# openSX70-dongle_v2-9.net
KiCad netlist of a schematic drawn in EAGLE
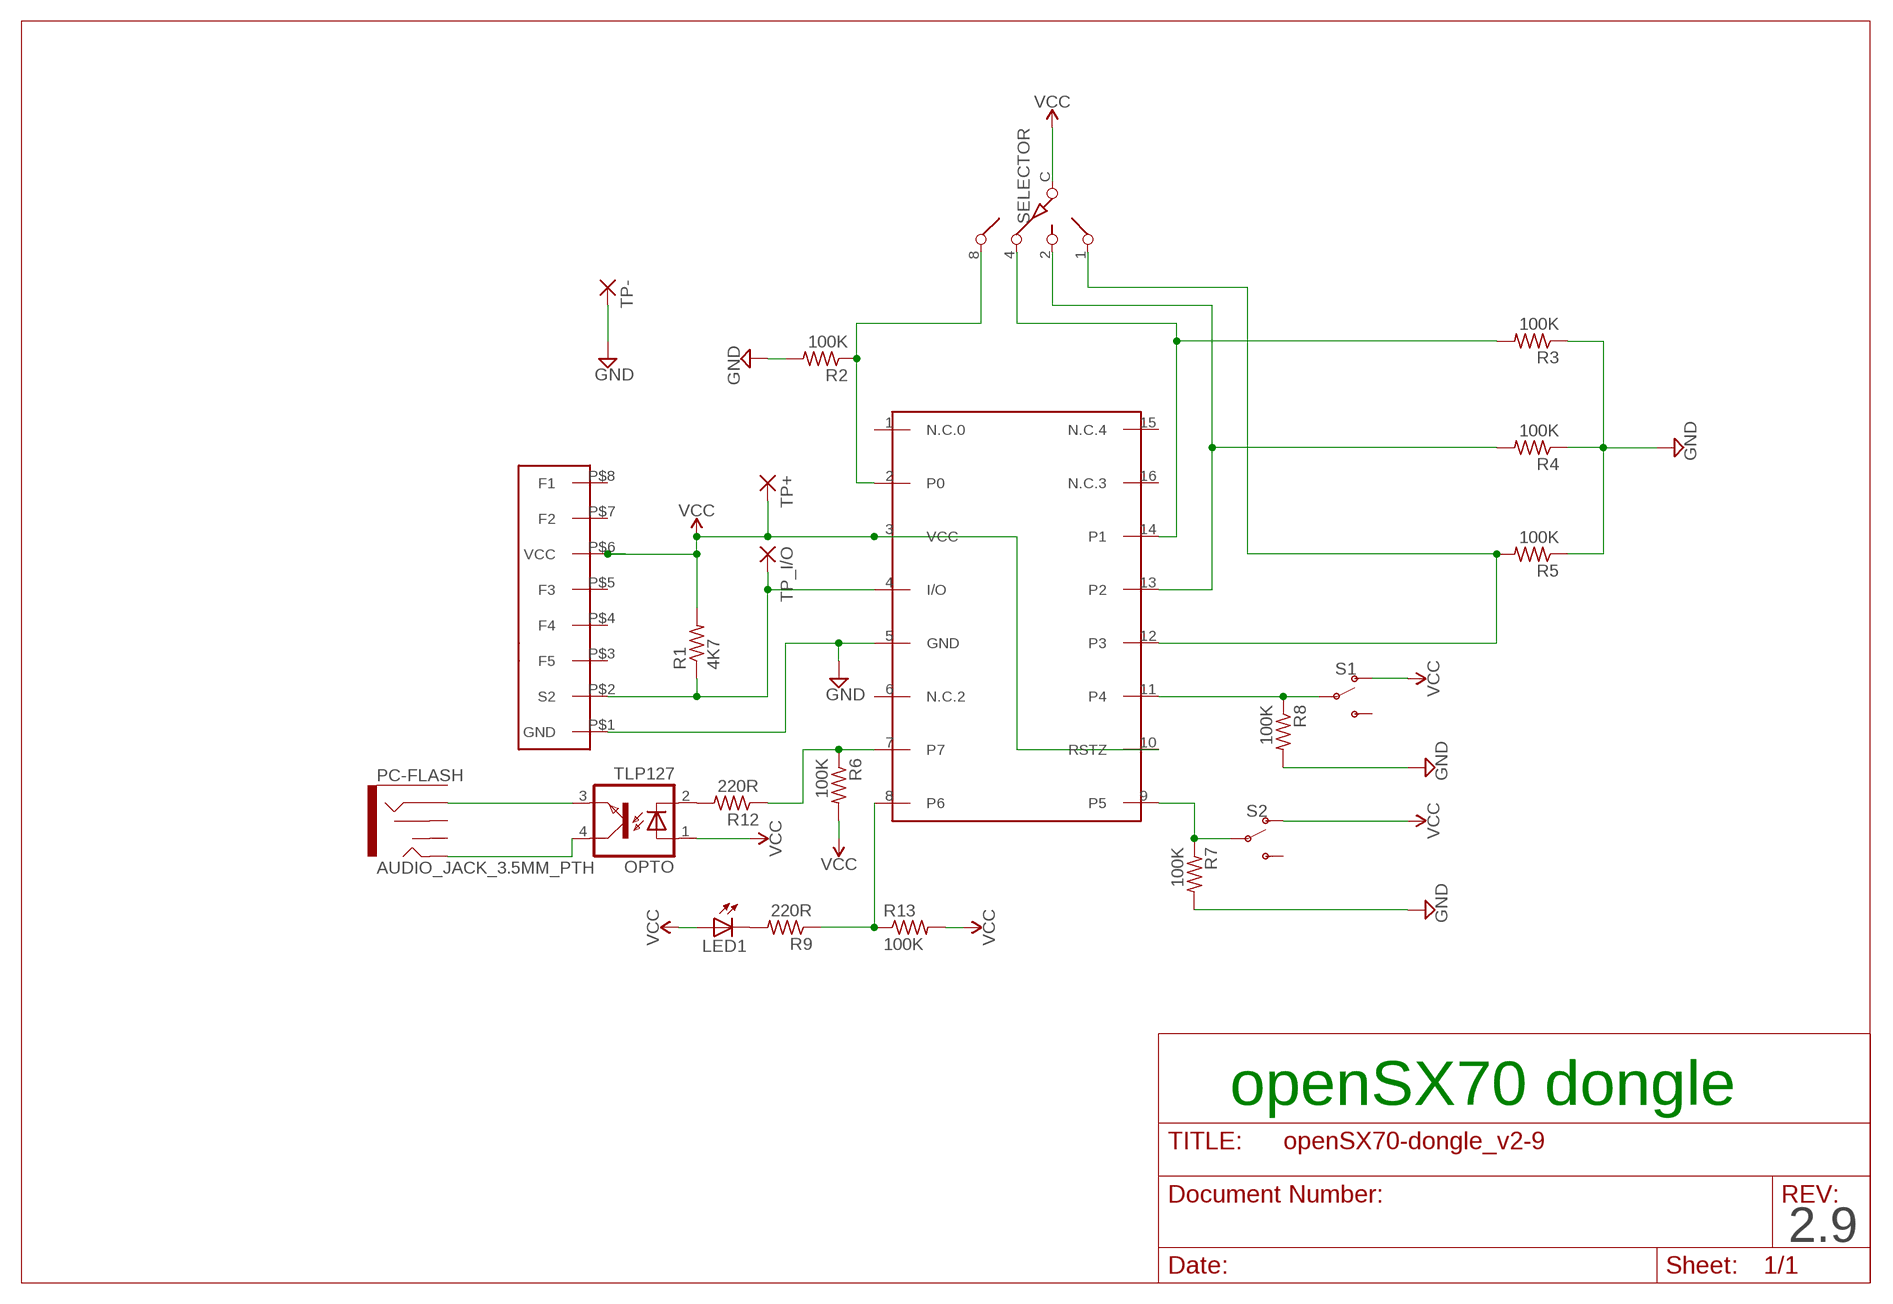
[diagram p0: schematic, sheet 1]

(export (version "E")
  (design (tool "Eeschema 10.0.6"))
  (components
    (comp (ref "DS2408")
      (value "DS2408")
      (footprint "eagle-import:SO16")
      (libsource (lib "eagle-import") (part "DS2408"))
    )
    (comp (ref "LED1")
      (value "LED3MM")
      (footprint "eagle-import:LED3MM")
      (libsource (lib "eagle-import") (part "LED3MM"))
    )
    (comp (ref "OPTO")
      (value "TLP127")
      (footprint "eagle-import:SO-4")
      (libsource (lib "eagle-import") (part "TLP127"))
    )
    (comp (ref "PC-FLASH")
      (value "AUDIO_JACK_3.5MM_PTH")
      (footprint "eagle-import:AUDIO-JACK")
      (libsource (lib "eagle-import") (part "AUDIO_JACK_3.5MM_PTH"))
    )
    (comp (ref "R1")
      (value "4K7")
      (footprint "eagle-import:M0805")
      (libsource (lib "eagle-import") (part "R-US_M0805"))
    )
    (comp (ref "R2")
      (value "100K")
      (footprint "eagle-import:M0805")
      (libsource (lib "eagle-import") (part "R-US_M0805"))
    )
    (comp (ref "R3")
      (value "100K")
      (footprint "eagle-import:M0805")
      (libsource (lib "eagle-import") (part "R-US_M0805"))
    )
    (comp (ref "R4")
      (value "100K")
      (footprint "eagle-import:M0805")
      (libsource (lib "eagle-import") (part "R-US_M0805"))
    )
    (comp (ref "R5")
      (value "100K")
      (footprint "eagle-import:M0805")
      (libsource (lib "eagle-import") (part "R-US_M0805"))
    )
    (comp (ref "R6")
      (value "100K")
      (footprint "eagle-import:M0805")
      (libsource (lib "eagle-import") (part "R-US_M0805"))
    )
    (comp (ref "R7")
      (value "100K")
      (footprint "eagle-import:M0805")
      (libsource (lib "eagle-import") (part "R-US_M0805"))
    )
    (comp (ref "R8")
      (value "100K")
      (footprint "eagle-import:M0805")
      (libsource (lib "eagle-import") (part "R-US_M0805"))
    )
    (comp (ref "R9")
      (value "220R")
      (footprint "eagle-import:M0805")
      (libsource (lib "eagle-import") (part "R-US_M0805"))
    )
    (comp (ref "R12")
      (value "220R")
      (footprint "eagle-import:M0805")
      (libsource (lib "eagle-import") (part "R-US_M0805"))
    )
    (comp (ref "R13")
      (value "100K")
      (footprint "eagle-import:M0805")
      (libsource (lib "eagle-import") (part "R-US_M0805"))
    )
    (comp (ref "S1")
      (value "SWITCH-SPDT-SMD-RIGHT-ANGLE")
      (footprint "eagle-import:SWITCH_SPST_SMD_A")
      (libsource (lib "eagle-import") (part "SWITCH-SPDT-SMD-RIGHT-ANGLE"))
    )
    (comp (ref "S2")
      (value "SWITCH-SPDT-SMD-RIGHT-ANGLE")
      (footprint "eagle-import:SWITCH_SPST_SMD_A")
      (libsource (lib "eagle-import") (part "SWITCH-SPDT-SMD-RIGHT-ANGLE"))
    )
    (comp (ref "SELECTOR")
      (value "SW-C16")
      (footprint "eagle-import:SW-C16")
      (libsource (lib "eagle-import") (part "SW-C16"))
    )
    (comp (ref "TP+")
      (value "SMD2")
      (footprint "eagle-import:SMD1,27-2,54")
      (libsource (lib "eagle-import") (part "SMD2"))
    )
    (comp (ref "TP-")
      (value "SMD2")
      (footprint "eagle-import:SMD1,27-2,54")
      (libsource (lib "eagle-import") (part "SMD2"))
    )
    (comp (ref "TP_I/O")
      (value "SMD2")
      (footprint "eagle-import:SMD1,27-2,54")
      (libsource (lib "eagle-import") (part "SMD2"))
    )
    (comp (ref "U$1")
      (value "FLASH-EDGE-CONNECTOR")
      (footprint "eagle-import:FLASH-EDGE-8")
      (libsource (lib "eagle-import") (part "FLASH-EDGE-CONNECTOR"))
    )
  )
  (nets
    (net (code "1") (name "GND") (class "Default")
      (node (ref "DS2408") (pin "5") (pinfunction "GND_5") (pintype "bidirectional"))
      (node (ref "R2") (pin "2") (pinfunction "2_2") (pintype "passive"))
      (node (ref "R3") (pin "1") (pinfunction "1_1") (pintype "passive"))
      (node (ref "R4") (pin "1") (pinfunction "1_1") (pintype "passive"))
      (node (ref "R5") (pin "1") (pinfunction "1_1") (pintype "passive"))
      (node (ref "R7") (pin "2") (pinfunction "2_2") (pintype "passive"))
      (node (ref "R8") (pin "2") (pinfunction "2_2") (pintype "passive"))
      (node (ref "TP-") (pin "1") (pinfunction "P_1") (pintype "passive"))
      (node (ref "U$1") (pin "P$1") (pinfunction "GND_P$1") (pintype "bidirectional"))
    )
    (net (code "2") (name "Net-(DS2408-I{slash}O)") (class "Default")
      (node (ref "DS2408") (pin "4") (pinfunction "I/O_4") (pintype "bidirectional"))
      (node (ref "R1") (pin "1") (pinfunction "1_1") (pintype "passive"))
      (node (ref "TP_I/O") (pin "1") (pinfunction "P_1") (pintype "passive"))
      (node (ref "U$1") (pin "P$2") (pinfunction "S2_P$2") (pintype "bidirectional"))
    )
    (net (code "3") (name "Net-(DS2408-P0)") (class "Default")
      (node (ref "DS2408") (pin "2") (pinfunction "P0_2") (pintype "bidirectional"))
      (node (ref "R2") (pin "1") (pinfunction "1_1") (pintype "passive"))
      (node (ref "SELECTOR") (pin "8") (pinfunction "8_8") (pintype "passive"))
    )
    (net (code "4") (name "Net-(DS2408-P1)") (class "Default")
      (node (ref "DS2408") (pin "14") (pinfunction "P1_14") (pintype "bidirectional"))
      (node (ref "R3") (pin "2") (pinfunction "2_2") (pintype "passive"))
      (node (ref "SELECTOR") (pin "4") (pinfunction "4_4") (pintype "passive"))
    )
    (net (code "5") (name "Net-(DS2408-P2)") (class "Default")
      (node (ref "DS2408") (pin "13") (pinfunction "P2_13") (pintype "bidirectional"))
      (node (ref "R4") (pin "2") (pinfunction "2_2") (pintype "passive"))
      (node (ref "SELECTOR") (pin "2") (pinfunction "2_2") (pintype "passive"))
    )
    (net (code "6") (name "Net-(DS2408-P3)") (class "Default")
      (node (ref "DS2408") (pin "12") (pinfunction "P3_12") (pintype "bidirectional"))
      (node (ref "R5") (pin "2") (pinfunction "2_2") (pintype "passive"))
      (node (ref "SELECTOR") (pin "1") (pinfunction "1_1") (pintype "passive"))
    )
    (net (code "7") (name "Net-(DS2408-P4)") (class "Default")
      (node (ref "DS2408") (pin "11") (pinfunction "P4_11") (pintype "bidirectional"))
      (node (ref "R8") (pin "1") (pinfunction "1_1") (pintype "passive"))
      (node (ref "S1") (pin "2") (pinfunction "P_2") (pintype "passive"))
    )
    (net (code "8") (name "Net-(DS2408-P5)") (class "Default")
      (node (ref "DS2408") (pin "9") (pinfunction "P5_9") (pintype "bidirectional"))
      (node (ref "R7") (pin "1") (pinfunction "1_1") (pintype "passive"))
      (node (ref "S2") (pin "2") (pinfunction "P_2") (pintype "passive"))
    )
    (net (code "9") (name "Net-(DS2408-P6)") (class "Default")
      (node (ref "DS2408") (pin "8") (pinfunction "P6_8") (pintype "bidirectional"))
      (node (ref "R13") (pin "1") (pinfunction "1_1") (pintype "passive"))
      (node (ref "R9") (pin "1") (pinfunction "1_1") (pintype "passive"))
    )
    (net (code "10") (name "Net-(DS2408-P7)") (class "Default")
      (node (ref "DS2408") (pin "7") (pinfunction "P7_7") (pintype "bidirectional"))
      (node (ref "R12") (pin "1") (pinfunction "1_1") (pintype "passive"))
      (node (ref "R6") (pin "1") (pinfunction "1_1") (pintype "passive"))
    )
    (net (code "11") (name "Net-(LED1-C)") (class "Default")
      (node (ref "LED1") (pin "K") (pinfunction "C_K") (pintype "passive"))
      (node (ref "R9") (pin "2") (pinfunction "2_2") (pintype "passive"))
    )
    (net (code "12") (name "Net-(OPTO-C)") (class "Default")
      (node (ref "OPTO") (pin "2") (pinfunction "C_2") (pintype "passive"))
      (node (ref "R12") (pin "2") (pinfunction "2_2") (pintype "passive"))
    )
    (net (code "13") (name "Net-(OPTO-COL)") (class "Default")
      (node (ref "OPTO") (pin "4") (pinfunction "COL_4") (pintype "passive"))
      (node (ref "PC-FLASH") (pin "TIP") (pinfunction "TIP_TIP") (pintype "bidirectional"))
    )
    (net (code "14") (name "Net-(OPTO-EMIT)") (class "Default")
      (node (ref "OPTO") (pin "3") (pinfunction "EMIT_3") (pintype "passive"))
      (node (ref "PC-FLASH") (pin "RING") (pinfunction "RING_RING") (pintype "bidirectional"))
    )
    (net (code "15") (name "VCC") (class "Default")
      (node (ref "DS2408") (pin "10") (pinfunction "RSTZ_10") (pintype "bidirectional"))
      (node (ref "DS2408") (pin "3") (pinfunction "VCC_3") (pintype "bidirectional"))
      (node (ref "LED1") (pin "A") (pinfunction "A_A") (pintype "passive"))
      (node (ref "OPTO") (pin "1") (pinfunction "A_1") (pintype "passive"))
      (node (ref "R1") (pin "2") (pinfunction "2_2") (pintype "passive"))
      (node (ref "R13") (pin "2") (pinfunction "2_2") (pintype "passive"))
      (node (ref "R6") (pin "2") (pinfunction "2_2") (pintype "passive"))
      (node (ref "S1") (pin "1") (pinfunction "O_1") (pintype "passive"))
      (node (ref "S2") (pin "1") (pinfunction "O_1") (pintype "passive"))
      (node (ref "SELECTOR") (pin "C") (pinfunction "C_C") (pintype "passive"))
      (node (ref "TP+") (pin "1") (pinfunction "P_1") (pintype "passive"))
      (node (ref "U$1") (pin "P$6") (pinfunction "VCC_P$6") (pintype "bidirectional"))
    )
    (net (code "16") (name "unconnected-(DS2408-N.C.0-Pad1)") (class "Default")
      (node (ref "DS2408") (pin "1") (pinfunction "N.C.0_1") (pintype "bidirectional"))
    )
    (net (code "17") (name "unconnected-(DS2408-N.C.2-Pad6)") (class "Default")
      (node (ref "DS2408") (pin "6") (pinfunction "N.C.2_6") (pintype "bidirectional"))
    )
    (net (code "18") (name "unconnected-(DS2408-N.C.3-Pad16)") (class "Default")
      (node (ref "DS2408") (pin "16") (pinfunction "N.C.3_16") (pintype "bidirectional"))
    )
    (net (code "19") (name "unconnected-(DS2408-N.C.4-Pad15)") (class "Default")
      (node (ref "DS2408") (pin "15") (pinfunction "N.C.4_15") (pintype "bidirectional"))
    )
    (net (code "20") (name "unconnected-(PC-FLASH-PadRSH)") (class "Default")
      (node (ref "PC-FLASH") (pin "RSH") (pinfunction "RSH_RSH") (pintype "bidirectional"))
    )
    (net (code "21") (name "unconnected-(PC-FLASH-PadSLEEVE)") (class "Default")
      (node (ref "PC-FLASH") (pin "SLEEVE") (pinfunction "SLEEVE_SLEEVE") (pintype "bidirectional"))
    )
    (net (code "22") (name "unconnected-(PC-FLASH-PadTSH)") (class "Default")
      (node (ref "PC-FLASH") (pin "TSH") (pinfunction "TSH_TSH") (pintype "bidirectional"))
    )
    (net (code "23") (name "unconnected-(S1-S-Pad3)") (class "Default")
      (node (ref "S1") (pin "3") (pinfunction "S_3") (pintype "passive"))
    )
    (net (code "24") (name "unconnected-(S2-S-Pad3)") (class "Default")
      (node (ref "S2") (pin "3") (pinfunction "S_3") (pintype "passive"))
    )
    (net (code "25") (name "unconnected-(U$1-F1-PadP$8)") (class "Default")
      (node (ref "U$1") (pin "P$8") (pinfunction "F1_P$8") (pintype "bidirectional"))
    )
    (net (code "26") (name "unconnected-(U$1-F2-PadP$7)") (class "Default")
      (node (ref "U$1") (pin "P$7") (pinfunction "F2_P$7") (pintype "bidirectional"))
    )
    (net (code "27") (name "unconnected-(U$1-F3-PadP$5)") (class "Default")
      (node (ref "U$1") (pin "P$5") (pinfunction "F3_P$5") (pintype "bidirectional"))
    )
    (net (code "28") (name "unconnected-(U$1-F4-PadP$4)") (class "Default")
      (node (ref "U$1") (pin "P$4") (pinfunction "F4_P$4") (pintype "bidirectional"))
    )
    (net (code "29") (name "unconnected-(U$1-F5-PadP$3)") (class "Default")
      (node (ref "U$1") (pin "P$3") (pinfunction "F5_P$3") (pintype "bidirectional"))
    )
  )
)
